# LVDS_RX.net
KiCad netlist of a schematic drawn in Altium Designer
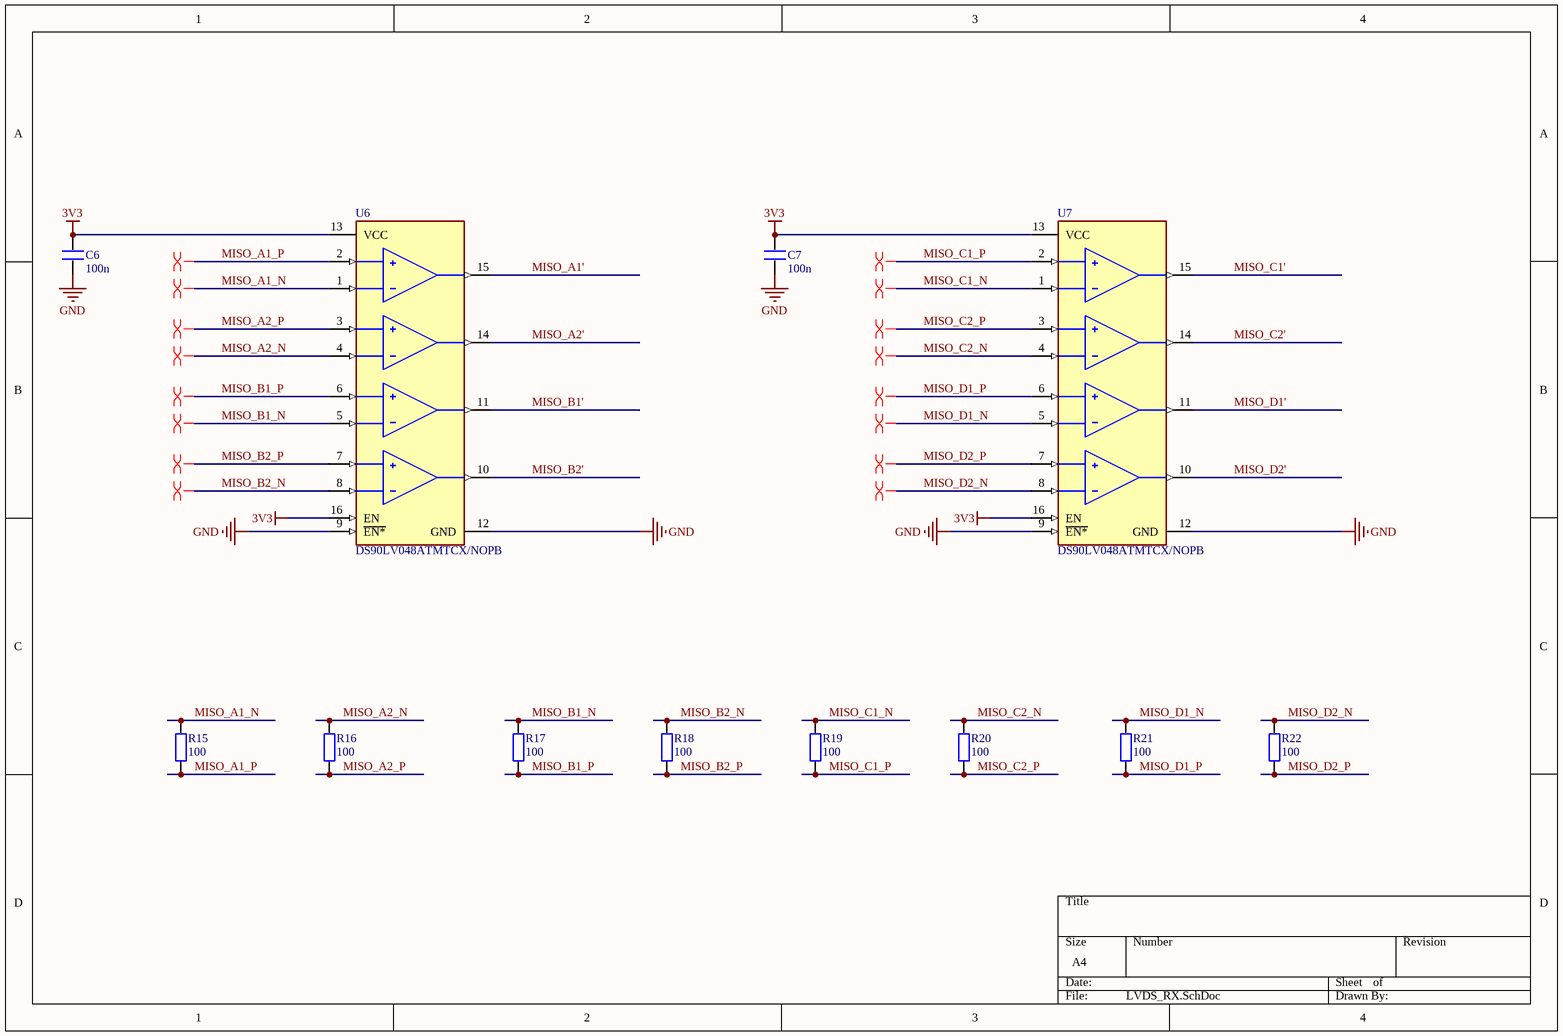
[diagram p0: LVDS_RX.SchDoc]

(export (version "E")
  (design (tool "Eeschema 10.0.6"))
  (components
    (comp (ref "C6") (value "100n") (footprint "C 0402_L") (libsource (lib "ZYNQ_开发板") (part "C_1")))
    (comp (ref "C7") (value "100n") (footprint "C 0402_L") (libsource (lib "ZYNQ_开发板") (part "C_1")))
    (comp (ref "R15")
      (value "100")
      (footprint "R 0402_L")
      (description "贴片电阻")
      (fields (field (name "版权归属") "源创客"))
      (libsource (lib "ZYNQ_开发板") (part "R_1"))
    )
    (comp (ref "R16")
      (value "100")
      (footprint "R 0402_L")
      (description "贴片电阻")
      (fields (field (name "版权归属") "源创客"))
      (libsource (lib "ZYNQ_开发板") (part "R_1"))
    )
    (comp (ref "R17")
      (value "100")
      (footprint "R 0402_L")
      (description "贴片电阻")
      (fields (field (name "版权归属") "源创客"))
      (libsource (lib "ZYNQ_开发板") (part "R_1"))
    )
    (comp (ref "R18")
      (value "100")
      (footprint "R 0402_L")
      (description "贴片电阻")
      (fields (field (name "版权归属") "源创客"))
      (libsource (lib "ZYNQ_开发板") (part "R_1"))
    )
    (comp (ref "R19")
      (value "100")
      (footprint "R 0402_L")
      (description "贴片电阻")
      (fields (field (name "版权归属") "源创客"))
      (libsource (lib "ZYNQ_开发板") (part "R_1"))
    )
    (comp (ref "R20")
      (value "100")
      (footprint "R 0402_L")
      (description "贴片电阻")
      (fields (field (name "版权归属") "源创客"))
      (libsource (lib "ZYNQ_开发板") (part "R_1"))
    )
    (comp (ref "R21")
      (value "100")
      (footprint "R 0402_L")
      (description "贴片电阻")
      (fields (field (name "版权归属") "源创客"))
      (libsource (lib "ZYNQ_开发板") (part "R_1"))
    )
    (comp (ref "R22")
      (value "100")
      (footprint "R 0402_L")
      (description "贴片电阻")
      (fields (field (name "版权归属") "源创客"))
      (libsource (lib "ZYNQ_开发板") (part "R_1"))
    )
    (comp (ref "U6")
      (value "DS90LV048ATMTCX/NOPB")
      (footprint "FP-PW0016A-MFG")
      (description "IC RECEIVER 0/4 16TSSOP")
      (libsource (lib "Altium Content Vault") (part "3c8acfd0125a7475389ff9e106063bb"))
    )
    (comp (ref "U7")
      (value "DS90LV048ATMTCX/NOPB")
      (footprint "FP-PW0016A-MFG")
      (description "IC RECEIVER 0/4 16TSSOP")
      (libsource (lib "Altium Content Vault") (part "3c8acfd0125a7475389ff9e106063bb"))
    )
  )
  (nets
    (net (code "1") (name "/MISO_A1'") (class "Default")
      (node (ref "U6") (pin "15") (pinfunction "ROUT1_15") (pintype "output"))
    )
    (net (code "2") (name "/MISO_A1_N") (class "Default")
      (node (ref "R15") (pin "2") (pinfunction "2_2") (pintype "passive"))
      (node (ref "U6") (pin "1") (pinfunction "RIN1-_1") (pintype "input"))
    )
    (net (code "3") (name "/MISO_A1_P") (class "Default")
      (node (ref "R15") (pin "1") (pinfunction "1_1") (pintype "passive"))
      (node (ref "U6") (pin "2") (pinfunction "RIN1+_2") (pintype "input"))
    )
    (net (code "4") (name "/MISO_A2'") (class "Default")
      (node (ref "U6") (pin "14") (pinfunction "ROUT2_14") (pintype "output"))
    )
    (net (code "5") (name "/MISO_A2_N") (class "Default")
      (node (ref "R16") (pin "2") (pinfunction "2_2") (pintype "passive"))
      (node (ref "U6") (pin "4") (pinfunction "RIN2-_4") (pintype "input"))
    )
    (net (code "6") (name "/MISO_A2_P") (class "Default")
      (node (ref "R16") (pin "1") (pinfunction "1_1") (pintype "passive"))
      (node (ref "U6") (pin "3") (pinfunction "RIN2+_3") (pintype "input"))
    )
    (net (code "7") (name "/MISO_B1'") (class "Default")
      (node (ref "U6") (pin "11") (pinfunction "ROUT3_11") (pintype "output"))
    )
    (net (code "8") (name "/MISO_B1_N") (class "Default")
      (node (ref "R17") (pin "2") (pinfunction "2_2") (pintype "passive"))
      (node (ref "U6") (pin "5") (pinfunction "RIN3-_5") (pintype "input"))
    )
    (net (code "9") (name "/MISO_B1_P") (class "Default")
      (node (ref "R17") (pin "1") (pinfunction "1_1") (pintype "passive"))
      (node (ref "U6") (pin "6") (pinfunction "RIN3+_6") (pintype "input"))
    )
    (net (code "10") (name "/MISO_B2'") (class "Default")
      (node (ref "U6") (pin "10") (pinfunction "ROUT4_10") (pintype "output"))
    )
    (net (code "11") (name "/MISO_B2_N") (class "Default")
      (node (ref "R18") (pin "2") (pinfunction "2_2") (pintype "passive"))
      (node (ref "U6") (pin "8") (pinfunction "RIN4-_8") (pintype "input"))
    )
    (net (code "12") (name "/MISO_B2_P") (class "Default")
      (node (ref "R18") (pin "1") (pinfunction "1_1") (pintype "passive"))
      (node (ref "U6") (pin "7") (pinfunction "RIN4+_7") (pintype "input"))
    )
    (net (code "13") (name "/MISO_C1'") (class "Default")
      (node (ref "U7") (pin "15") (pinfunction "ROUT1_15") (pintype "output"))
    )
    (net (code "14") (name "/MISO_C1_N") (class "Default")
      (node (ref "R19") (pin "2") (pinfunction "2_2") (pintype "passive"))
      (node (ref "U7") (pin "1") (pinfunction "RIN1-_1") (pintype "input"))
    )
    (net (code "15") (name "/MISO_C1_P") (class "Default")
      (node (ref "R19") (pin "1") (pinfunction "1_1") (pintype "passive"))
      (node (ref "U7") (pin "2") (pinfunction "RIN1+_2") (pintype "input"))
    )
    (net (code "16") (name "/MISO_C2'") (class "Default")
      (node (ref "U7") (pin "14") (pinfunction "ROUT2_14") (pintype "output"))
    )
    (net (code "17") (name "/MISO_C2_N") (class "Default")
      (node (ref "R20") (pin "2") (pinfunction "2_2") (pintype "passive"))
      (node (ref "U7") (pin "4") (pinfunction "RIN2-_4") (pintype "input"))
    )
    (net (code "18") (name "/MISO_C2_P") (class "Default")
      (node (ref "R20") (pin "1") (pinfunction "1_1") (pintype "passive"))
      (node (ref "U7") (pin "3") (pinfunction "RIN2+_3") (pintype "input"))
    )
    (net (code "19") (name "/MISO_D1'") (class "Default")
      (node (ref "U7") (pin "11") (pinfunction "ROUT3_11") (pintype "output"))
    )
    (net (code "20") (name "/MISO_D1_N") (class "Default")
      (node (ref "R21") (pin "2") (pinfunction "2_2") (pintype "passive"))
      (node (ref "U7") (pin "5") (pinfunction "RIN3-_5") (pintype "input"))
    )
    (net (code "21") (name "/MISO_D1_P") (class "Default")
      (node (ref "R21") (pin "1") (pinfunction "1_1") (pintype "passive"))
      (node (ref "U7") (pin "6") (pinfunction "RIN3+_6") (pintype "input"))
    )
    (net (code "22") (name "/MISO_D2'") (class "Default")
      (node (ref "U7") (pin "10") (pinfunction "ROUT4_10") (pintype "output"))
    )
    (net (code "23") (name "/MISO_D2_N") (class "Default")
      (node (ref "R22") (pin "2") (pinfunction "2_2") (pintype "passive"))
      (node (ref "U7") (pin "8") (pinfunction "RIN4-_8") (pintype "input"))
    )
    (net (code "24") (name "/MISO_D2_P") (class "Default")
      (node (ref "R22") (pin "1") (pinfunction "1_1") (pintype "passive"))
      (node (ref "U7") (pin "7") (pinfunction "RIN4+_7") (pintype "input"))
    )
    (net (code "25") (name "3V3") (class "Default")
      (node (ref "C6") (pin "2") (pintype "passive"))
      (node (ref "C7") (pin "2") (pintype "passive"))
      (node (ref "U6") (pin "13") (pinfunction "VCC_13") (pintype "power_in"))
      (node (ref "U6") (pin "16") (pinfunction "EN_16") (pintype "input"))
      (node (ref "U7") (pin "13") (pinfunction "VCC_13") (pintype "power_in"))
      (node (ref "U7") (pin "16") (pinfunction "EN_16") (pintype "input"))
    )
    (net (code "26") (name "GND") (class "Default")
      (node (ref "C6") (pin "1") (pintype "passive"))
      (node (ref "C7") (pin "1") (pintype "passive"))
      (node (ref "U6") (pin "12") (pinfunction "GND_12") (pintype "power_in"))
      (node (ref "U6") (pin "9") (pinfunction "~{EN*}_9") (pintype "input"))
      (node (ref "U7") (pin "12") (pinfunction "GND_12") (pintype "power_in"))
      (node (ref "U7") (pin "9") (pinfunction "~{EN*}_9") (pintype "input"))
    )
  )
)
